# DesignChallenge1.net
KiCad netlist of a schematic drawn in Altium Designer
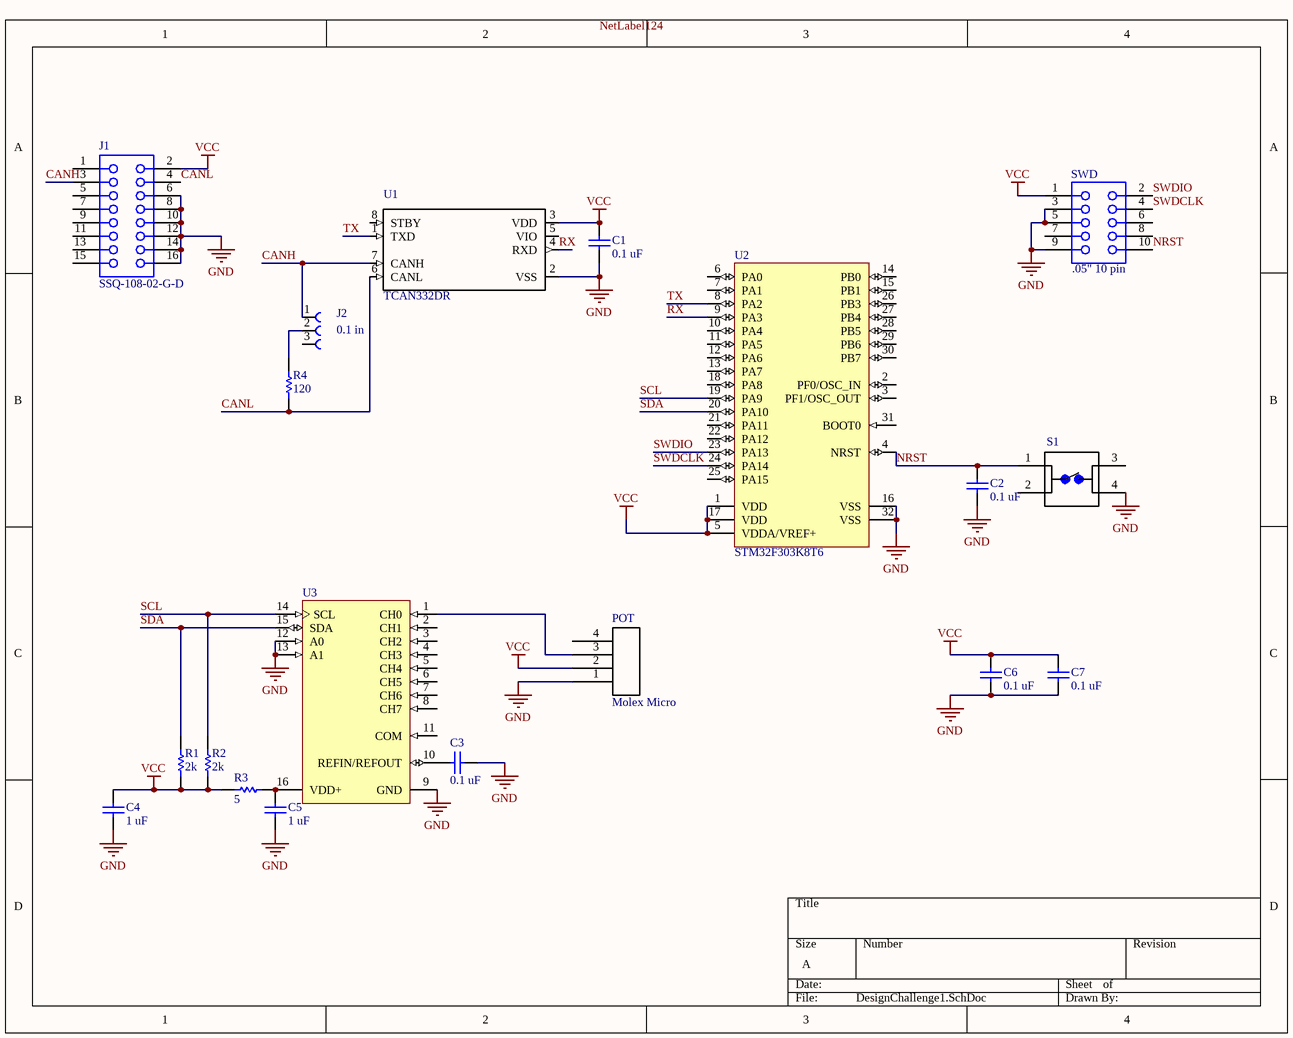
[diagram p0: DesignChallenge1.SchDoc]

(export (version "E")
  (design (tool "Eeschema 10.0.6"))
  (components
    (comp (ref "C1")
      (value "0.1 uF")
      (footprint "CAPC0805(2012)145_N")
      (description "CAP 470pF 100V ±2% 0805 (2012 Metric) Thickness 1.45mm SMD")
      (fields (field (name "TOLERANCE") "Â±2%"))
      (libsource (lib "Altium Content Vault") (part "CAP"))
    )
    (comp (ref "C2")
      (value "0.1 uF")
      (footprint "CAPC0805(2012)145_N")
      (description "CAP 470pF 100V ±2% 0805 (2012 Metric) Thickness 1.45mm SMD")
      (fields (field (name "TOLERANCE") "Â±2%"))
      (libsource (lib "Altium Content Vault") (part "CAP"))
    )
    (comp (ref "C3")
      (value "0.1 uF")
      (footprint "CAPC0805(2012)145_N")
      (description "CAP 470pF 100V ±2% 0805 (2012 Metric) Thickness 1.45mm SMD")
      (fields (field (name "TOLERANCE") "Â±2%"))
      (libsource (lib "Altium Content Vault") (part "CAP"))
    )
    (comp (ref "C4")
      (value "1 uF")
      (footprint "CAPC0805(2012)145_N")
      (description "CAP 470pF 100V ±2% 0805 (2012 Metric) Thickness 1.45mm SMD")
      (fields (field (name "TOLERANCE") "Â±2%"))
      (libsource (lib "Altium Content Vault") (part "CAP"))
    )
    (comp (ref "C5")
      (value "1 uF")
      (footprint "CAPC0805(2012)145_N")
      (description "CAP 470pF 100V ±2% 0805 (2012 Metric) Thickness 1.45mm SMD")
      (fields (field (name "TOLERANCE") "Â±2%"))
      (libsource (lib "Altium Content Vault") (part "CAP"))
    )
    (comp (ref "C6")
      (value "0.1 uF")
      (footprint "CAPC0805(2012)145_N")
      (description "CAP 470pF 100V ±2% 0805 (2012 Metric) Thickness 1.45mm SMD")
      (fields (field (name "TOLERANCE") "Â±2%"))
      (libsource (lib "Altium Content Vault") (part "CAP"))
    )
    (comp (ref "C7")
      (value "0.1 uF")
      (footprint "CAPC0805(2012)145_N")
      (description "CAP 470pF 100V ±2% 0805 (2012 Metric) Thickness 1.45mm SMD")
      (fields (field (name "TOLERANCE") "Â±2%"))
      (libsource (lib "Altium Content Vault") (part "CAP"))
    )
    (comp (ref "J1")
      (value "SSQ-108-02-G-D")
      (footprint "SMTC-SSQ-108-02-X-D")
      (description "SQ Post Socket, Through-hole, Vertical, -55 to 125 degC, 2.54 mm Pitch, 16-Pin, Female, RoHS")
      (fields (field (name "MANUFACTURER") "Samtec"))
      (libsource (lib "Headers") (part "CMP-1023-00300-1"))
    )
    (comp (ref "J2")
      (value "0.1 in")
      (footprint "61300311121")
      (description "Board-To-Board Connector, Vertical, WR-PHD Series, Through Hole, Header, 3, 2.54 mm")
      (fields (field (name "MP") "61300311121") (field (name "MF") "Wurth Electronics"))
      (libsource (lib "61300311121") (part "61300311121"))
    )
    (comp (ref "POT")
      (value "Molex Micro")
      (footprint "0430450427")
      (description "Molex micro-fit 3.0 dual row header. P/N 0430450427")
      (libsource (lib "Connector Schematic Symbols") (part "Molex micro-fit 4-pin (Single row schematic)"))
    )
    (comp (ref "R1")
      (value "2k")
      (footprint "RESC0805(2012)_N")
      (description "160R 0.125W 1% 0805 (2012 Metric)  SMD")
      (fields (field (name "TOLERANCE") "1 %") (field (name "POWER") "0.125 W"))
      (libsource (lib "Altium Content Vault") (part "RES"))
    )
    (comp (ref "R2")
      (value "2k")
      (footprint "RESC0805(2012)_N")
      (description "160R 0.125W 1% 0805 (2012 Metric)  SMD")
      (fields (field (name "TOLERANCE") "1 %") (field (name "POWER") "0.125 W"))
      (libsource (lib "Altium Content Vault") (part "RES"))
    )
    (comp (ref "R3")
      (value "5")
      (footprint "RESC0805(2012)_N")
      (description "160R 0.125W 1% 0805 (2012 Metric)  SMD")
      (fields (field (name "TOLERANCE") "1 %") (field (name "POWER") "0.125 W"))
      (libsource (lib "Altium Content Vault") (part "RES"))
    )
    (comp (ref "R4")
      (value "120")
      (footprint "RESC0805(2012)_N")
      (description "160R 0.125W 1% 0805 (2012 Metric)  SMD")
      (fields (field (name "TOLERANCE") "1 %") (field (name "POWER") "0.125 W"))
      (libsource (lib "Altium Content Vault") (part "RES"))
    )
    (comp (ref "S1")
      (value "1825910-7")
      (footprint "*SW_1825910-7")
      (description "FSM4JAH=6MM TACT SWITCH, HIGH TEMP")
      (fields (field (name "MF") "TE Connectivity"))
      (libsource (lib "1825910-7") (part "1825910-7"))
    )
    (comp (ref "SWD")
      (value ".05\" 10 pin")
      (footprint "PCE-FH127H432-10-SNGRH-2.4")
      (description "Female Header, Pitch 1.27 mm, 2x5 Position, Height 4.3 mm, Tail Length 2.4 mm")
      (fields
        (field (name "PARTNUMBER") "FH127H432-10-SNGRH-2.4")
        (field (name "MANUFACTURER") "Pinchao Electronic")
      )
      (libsource (lib "Altium Content Vault") (part "PCE-HDR-2P-F-R10"))
    )
    (comp (ref "U1")
      (value "TCAN332DR")
      (footprint "CAN Tranceiver (1):Model Name")
      (description "Microchip MCP2562-E/SN, CAN Transceiver 1MBps 1-channel IEC 61000-4-2, 8-Pin SOIC")
      (fields (field (name "MF") "Microchip") (field (name "MP") "MCP2562-E/SN"))
      (libsource (lib "CAN Tranceiver") (part "CAN Tranceiver"))
    )
    (comp (ref "U2")
      (value "STM32F303K8T6")
      (footprint "STM-LQFP32_M")
      (libsource (lib "Altium Content Vault") (part "MC-ARM-STM32F303-LQFP32"))
    )
    (comp (ref "U3")
      (value "~")
      (footprint "TI-PW16_M")
      (fields (field (name "MANUFACTURER") "Texas Instruments") (field (name "PARTNUMBER") "ADS7828EB/250"))
      (libsource (lib "Altium Content Vault") (part "TI-ADS7828PW16"))
    )
  )
  (nets
    (net (code "1") (name "/CANH") (class "Default")
      (node (ref "J1") (pin "3") (pinfunction "3_3") (pintype "passive"))
      (node (ref "J2") (pin "1") (pinfunction "1_1") (pintype "passive"))
      (node (ref "U1") (pin "7") (pinfunction "CANH_7") (pintype "input"))
    )
    (net (code "2") (name "/CANL") (class "Default")
      (node (ref "J1") (pin "4") (pinfunction "4_4") (pintype "passive"))
      (node (ref "R4") (pin "2") (pinfunction "2_2") (pintype "passive"))
      (node (ref "U1") (pin "6") (pinfunction "CANL_6") (pintype "input"))
    )
    (net (code "3") (name "/NRST") (class "Default")
      (node (ref "C2") (pin "2") (pinfunction "2_2") (pintype "passive"))
      (node (ref "S1") (pin "1") (pinfunction "1_1") (pintype "passive"))
      (node (ref "SWD") (pin "10") (pinfunction "10_10") (pintype "passive"))
      (node (ref "U2") (pin "4") (pinfunction "NRST_4") (pintype "bidirectional"))
    )
    (net (code "5") (name "/RX") (class "Default")
      (node (ref "U1") (pin "4") (pinfunction "RXD_4") (pintype "output"))
      (node (ref "U2") (pin "9") (pinfunction "PA3_9") (pintype "bidirectional"))
    )
    (net (code "6") (name "/SCL") (class "Default")
      (node (ref "R2") (pin "1") (pinfunction "1_1") (pintype "passive"))
      (node (ref "U2") (pin "19") (pinfunction "PA9_19") (pintype "bidirectional"))
      (node (ref "U3") (pin "14") (pinfunction "SCL_14") (pintype "input"))
    )
    (net (code "7") (name "/SDA") (class "Default")
      (node (ref "R1") (pin "1") (pinfunction "1_1") (pintype "passive"))
      (node (ref "U2") (pin "20") (pinfunction "PA10_20") (pintype "bidirectional"))
      (node (ref "U3") (pin "15") (pinfunction "SDA_15") (pintype "bidirectional"))
    )
    (net (code "8") (name "/SWDCLK") (class "Default")
      (node (ref "SWD") (pin "4") (pinfunction "4_4") (pintype "passive"))
      (node (ref "U2") (pin "24") (pinfunction "PA14_24") (pintype "bidirectional"))
    )
    (net (code "9") (name "/SWDIO") (class "Default")
      (node (ref "SWD") (pin "2") (pinfunction "2_2") (pintype "passive"))
      (node (ref "U2") (pin "23") (pinfunction "PA13_23") (pintype "bidirectional"))
    )
    (net (code "10") (name "/TX") (class "Default")
      (node (ref "U1") (pin "1") (pinfunction "TXD_1") (pintype "input"))
      (node (ref "U2") (pin "8") (pinfunction "PA2_8") (pintype "bidirectional"))
    )
    (net (code "11") (name "GND") (class "Default")
      (node (ref "C1") (pin "1") (pinfunction "1_1") (pintype "passive"))
      (node (ref "C2") (pin "1") (pinfunction "1_1") (pintype "passive"))
      (node (ref "C3") (pin "2") (pinfunction "2_2") (pintype "passive"))
      (node (ref "C4") (pin "1") (pinfunction "1_1") (pintype "passive"))
      (node (ref "C5") (pin "1") (pinfunction "1_1") (pintype "passive"))
      (node (ref "C6") (pin "1") (pinfunction "1_1") (pintype "passive"))
      (node (ref "C7") (pin "1") (pinfunction "1_1") (pintype "passive"))
      (node (ref "J1") (pin "10") (pinfunction "10_10") (pintype "passive"))
      (node (ref "J1") (pin "12") (pinfunction "12_12") (pintype "passive"))
      (node (ref "J1") (pin "14") (pinfunction "14_14") (pintype "passive"))
      (node (ref "J1") (pin "16") (pinfunction "16_16") (pintype "passive"))
      (node (ref "J1") (pin "6") (pinfunction "6_6") (pintype "passive"))
      (node (ref "J1") (pin "8") (pinfunction "8_8") (pintype "passive"))
      (node (ref "POT") (pin "1") (pintype "passive"))
      (node (ref "S1") (pin "4") (pinfunction "4_4") (pintype "passive"))
      (node (ref "SWD") (pin "3") (pinfunction "3_3") (pintype "passive"))
      (node (ref "SWD") (pin "5") (pinfunction "5_5") (pintype "passive"))
      (node (ref "SWD") (pin "9") (pinfunction "9_9") (pintype "passive"))
      (node (ref "U1") (pin "2") (pinfunction "VSS_2") (pintype "power_in"))
      (node (ref "U2") (pin "16") (pinfunction "VSS_16") (pintype "power_in"))
      (node (ref "U2") (pin "32") (pinfunction "VSS_32") (pintype "power_in"))
      (node (ref "U3") (pin "12") (pinfunction "A0_12") (pintype "input"))
      (node (ref "U3") (pin "13") (pinfunction "A1_13") (pintype "input"))
      (node (ref "U3") (pin "9") (pinfunction "GND_9") (pintype "power_in"))
    )
    (net (code "12") (name "Net-(J2-Pad2)") (class "Default")
      (node (ref "J2") (pin "2") (pinfunction "2_2") (pintype "passive"))
      (node (ref "R4") (pin "1") (pinfunction "1_1") (pintype "passive"))
    )
    (net (code "13") (name "Net-(U3-CH0)") (class "Default")
      (node (ref "POT") (pin "3") (pintype "passive"))
      (node (ref "U3") (pin "1") (pinfunction "CH0_1") (pintype "input"))
    )
    (net (code "14") (name "Net-(U3-REFIN{slash}REFOUT)") (class "Default")
      (node (ref "C3") (pin "1") (pinfunction "1_1") (pintype "passive"))
      (node (ref "U3") (pin "10") (pinfunction "REFIN/REFOUT_10") (pintype "bidirectional"))
    )
    (net (code "15") (name "Net-(U3-VDD+)") (class "Default")
      (node (ref "C5") (pin "2") (pinfunction "2_2") (pintype "passive"))
      (node (ref "R3") (pin "1") (pinfunction "1_1") (pintype "passive"))
      (node (ref "U3") (pin "16") (pinfunction "VDD+_16") (pintype "power_in"))
    )
    (net (code "16") (name "VCC") (class "Default")
      (node (ref "C1") (pin "2") (pinfunction "2_2") (pintype "passive"))
      (node (ref "C4") (pin "2") (pinfunction "2_2") (pintype "passive"))
      (node (ref "C6") (pin "2") (pinfunction "2_2") (pintype "passive"))
      (node (ref "C7") (pin "2") (pinfunction "2_2") (pintype "passive"))
      (node (ref "J1") (pin "2") (pinfunction "2_2") (pintype "passive"))
      (node (ref "POT") (pin "2") (pintype "passive"))
      (node (ref "R1") (pin "2") (pinfunction "2_2") (pintype "passive"))
      (node (ref "R2") (pin "2") (pinfunction "2_2") (pintype "passive"))
      (node (ref "R3") (pin "2") (pinfunction "2_2") (pintype "passive"))
      (node (ref "SWD") (pin "1") (pinfunction "1_1") (pintype "passive"))
      (node (ref "U1") (pin "3") (pinfunction "VDD_3") (pintype "power_in"))
      (node (ref "U2") (pin "1") (pinfunction "VDD_1") (pintype "power_in"))
      (node (ref "U2") (pin "17") (pinfunction "VDD_17") (pintype "power_in"))
      (node (ref "U2") (pin "5") (pinfunction "VDDA/VREF+_5") (pintype "power_in"))
    )
    (net (code "17") (name "unconnected-(J1-Pad1)") (class "Default")
      (node (ref "J1") (pin "1") (pinfunction "1_1") (pintype "passive"))
    )
    (net (code "18") (name "unconnected-(J1-Pad5)") (class "Default")
      (node (ref "J1") (pin "5") (pinfunction "5_5") (pintype "passive"))
    )
    (net (code "19") (name "unconnected-(J1-Pad7)") (class "Default")
      (node (ref "J1") (pin "7") (pinfunction "7_7") (pintype "passive"))
    )
    (net (code "20") (name "unconnected-(J1-Pad9)") (class "Default")
      (node (ref "J1") (pin "9") (pinfunction "9_9") (pintype "passive"))
    )
    (net (code "21") (name "unconnected-(J1-Pad11)") (class "Default")
      (node (ref "J1") (pin "11") (pinfunction "11_11") (pintype "passive"))
    )
    (net (code "22") (name "unconnected-(J1-Pad13)") (class "Default")
      (node (ref "J1") (pin "13") (pinfunction "13_13") (pintype "passive"))
    )
    (net (code "23") (name "unconnected-(J1-Pad15)") (class "Default")
      (node (ref "J1") (pin "15") (pinfunction "15_15") (pintype "passive"))
    )
    (net (code "24") (name "unconnected-(J2-Pad3)") (class "Default")
      (node (ref "J2") (pin "3") (pinfunction "3_3") (pintype "passive"))
    )
    (net (code "25") (name "unconnected-(POT-Pad4)") (class "Default")
      (node (ref "POT") (pin "4") (pintype "passive"))
    )
    (net (code "26") (name "unconnected-(S1-Pad2)") (class "Default")
      (node (ref "S1") (pin "2") (pinfunction "2_2") (pintype "passive"))
    )
    (net (code "27") (name "unconnected-(S1-Pad3)") (class "Default")
      (node (ref "S1") (pin "3") (pinfunction "3_3") (pintype "passive"))
    )
    (net (code "28") (name "unconnected-(SWD-Pad6)") (class "Default")
      (node (ref "SWD") (pin "6") (pinfunction "6_6") (pintype "passive"))
    )
    (net (code "29") (name "unconnected-(SWD-Pad7)") (class "Default")
      (node (ref "SWD") (pin "7") (pinfunction "7_7") (pintype "passive"))
    )
    (net (code "30") (name "unconnected-(SWD-Pad8)") (class "Default")
      (node (ref "SWD") (pin "8") (pinfunction "8_8") (pintype "passive"))
    )
    (net (code "31") (name "unconnected-(U1-STBY-Pad8)") (class "Default")
      (node (ref "U1") (pin "8") (pinfunction "STBY_8") (pintype "input"))
    )
    (net (code "32") (name "unconnected-(U1-VIO-Pad5)") (class "Default")
      (node (ref "U1") (pin "5") (pinfunction "VIO_5") (pintype "power_in"))
    )
    (net (code "33") (name "unconnected-(U2-BOOT0-Pad31)") (class "Default")
      (node (ref "U2") (pin "31") (pinfunction "BOOT0_31") (pintype "input"))
    )
    (net (code "34") (name "unconnected-(U2-PA0-Pad6)") (class "Default")
      (node (ref "U2") (pin "6") (pinfunction "PA0_6") (pintype "bidirectional"))
    )
    (net (code "35") (name "unconnected-(U2-PA1-Pad7)") (class "Default")
      (node (ref "U2") (pin "7") (pinfunction "PA1_7") (pintype "bidirectional"))
    )
    (net (code "36") (name "unconnected-(U2-PA4-Pad10)") (class "Default")
      (node (ref "U2") (pin "10") (pinfunction "PA4_10") (pintype "bidirectional"))
    )
    (net (code "37") (name "unconnected-(U2-PA5-Pad11)") (class "Default")
      (node (ref "U2") (pin "11") (pinfunction "PA5_11") (pintype "bidirectional"))
    )
    (net (code "38") (name "unconnected-(U2-PA6-Pad12)") (class "Default")
      (node (ref "U2") (pin "12") (pinfunction "PA6_12") (pintype "bidirectional"))
    )
    (net (code "39") (name "unconnected-(U2-PA7-Pad13)") (class "Default")
      (node (ref "U2") (pin "13") (pinfunction "PA7_13") (pintype "bidirectional"))
    )
    (net (code "40") (name "unconnected-(U2-PA8-Pad18)") (class "Default")
      (node (ref "U2") (pin "18") (pinfunction "PA8_18") (pintype "bidirectional"))
    )
    (net (code "41") (name "unconnected-(U2-PA11-Pad21)") (class "Default")
      (node (ref "U2") (pin "21") (pinfunction "PA11_21") (pintype "bidirectional"))
    )
    (net (code "42") (name "unconnected-(U2-PA12-Pad22)") (class "Default")
      (node (ref "U2") (pin "22") (pinfunction "PA12_22") (pintype "bidirectional"))
    )
    (net (code "43") (name "unconnected-(U2-PA15-Pad25)") (class "Default")
      (node (ref "U2") (pin "25") (pinfunction "PA15_25") (pintype "bidirectional"))
    )
    (net (code "44") (name "unconnected-(U2-PB0-Pad14)") (class "Default")
      (node (ref "U2") (pin "14") (pinfunction "PB0_14") (pintype "bidirectional"))
    )
    (net (code "45") (name "unconnected-(U2-PB1-Pad15)") (class "Default")
      (node (ref "U2") (pin "15") (pinfunction "PB1_15") (pintype "bidirectional"))
    )
    (net (code "46") (name "unconnected-(U2-PB3-Pad26)") (class "Default")
      (node (ref "U2") (pin "26") (pinfunction "PB3_26") (pintype "bidirectional"))
    )
    (net (code "47") (name "unconnected-(U2-PB4-Pad27)") (class "Default")
      (node (ref "U2") (pin "27") (pinfunction "PB4_27") (pintype "bidirectional"))
    )
    (net (code "48") (name "unconnected-(U2-PB5-Pad28)") (class "Default")
      (node (ref "U2") (pin "28") (pinfunction "PB5_28") (pintype "bidirectional"))
    )
    (net (code "49") (name "unconnected-(U2-PB6-Pad29)") (class "Default")
      (node (ref "U2") (pin "29") (pinfunction "PB6_29") (pintype "bidirectional"))
    )
    (net (code "50") (name "unconnected-(U2-PB7-Pad30)") (class "Default")
      (node (ref "U2") (pin "30") (pinfunction "PB7_30") (pintype "bidirectional"))
    )
    (net (code "51") (name "unconnected-(U2-PF0{slash}OSC_IN-Pad2)") (class "Default")
      (node (ref "U2") (pin "2") (pinfunction "PF0/OSC_IN_2") (pintype "bidirectional"))
    )
    (net (code "52") (name "unconnected-(U2-PF1{slash}OSC_OUT-Pad3)") (class "Default")
      (node (ref "U2") (pin "3") (pinfunction "PF1/OSC_OUT_3") (pintype "bidirectional"))
    )
    (net (code "53") (name "unconnected-(U3-CH1-Pad2)") (class "Default")
      (node (ref "U3") (pin "2") (pinfunction "CH1_2") (pintype "input"))
    )
    (net (code "54") (name "unconnected-(U3-CH2-Pad3)") (class "Default")
      (node (ref "U3") (pin "3") (pinfunction "CH2_3") (pintype "input"))
    )
    (net (code "55") (name "unconnected-(U3-CH3-Pad4)") (class "Default")
      (node (ref "U3") (pin "4") (pinfunction "CH3_4") (pintype "input"))
    )
    (net (code "56") (name "unconnected-(U3-CH4-Pad5)") (class "Default")
      (node (ref "U3") (pin "5") (pinfunction "CH4_5") (pintype "input"))
    )
    (net (code "57") (name "unconnected-(U3-CH5-Pad6)") (class "Default")
      (node (ref "U3") (pin "6") (pinfunction "CH5_6") (pintype "input"))
    )
    (net (code "58") (name "unconnected-(U3-CH6-Pad7)") (class "Default")
      (node (ref "U3") (pin "7") (pinfunction "CH6_7") (pintype "input"))
    )
    (net (code "59") (name "unconnected-(U3-CH7-Pad8)") (class "Default")
      (node (ref "U3") (pin "8") (pinfunction "CH7_8") (pintype "input"))
    )
    (net (code "60") (name "unconnected-(U3-COM-Pad11)") (class "Default")
      (node (ref "U3") (pin "11") (pinfunction "COM_11") (pintype "input"))
    )
  )
)
